# SAMV71_Xplained_Ultra_Connectors.net
KiCad netlist of a schematic drawn in Altium Designer
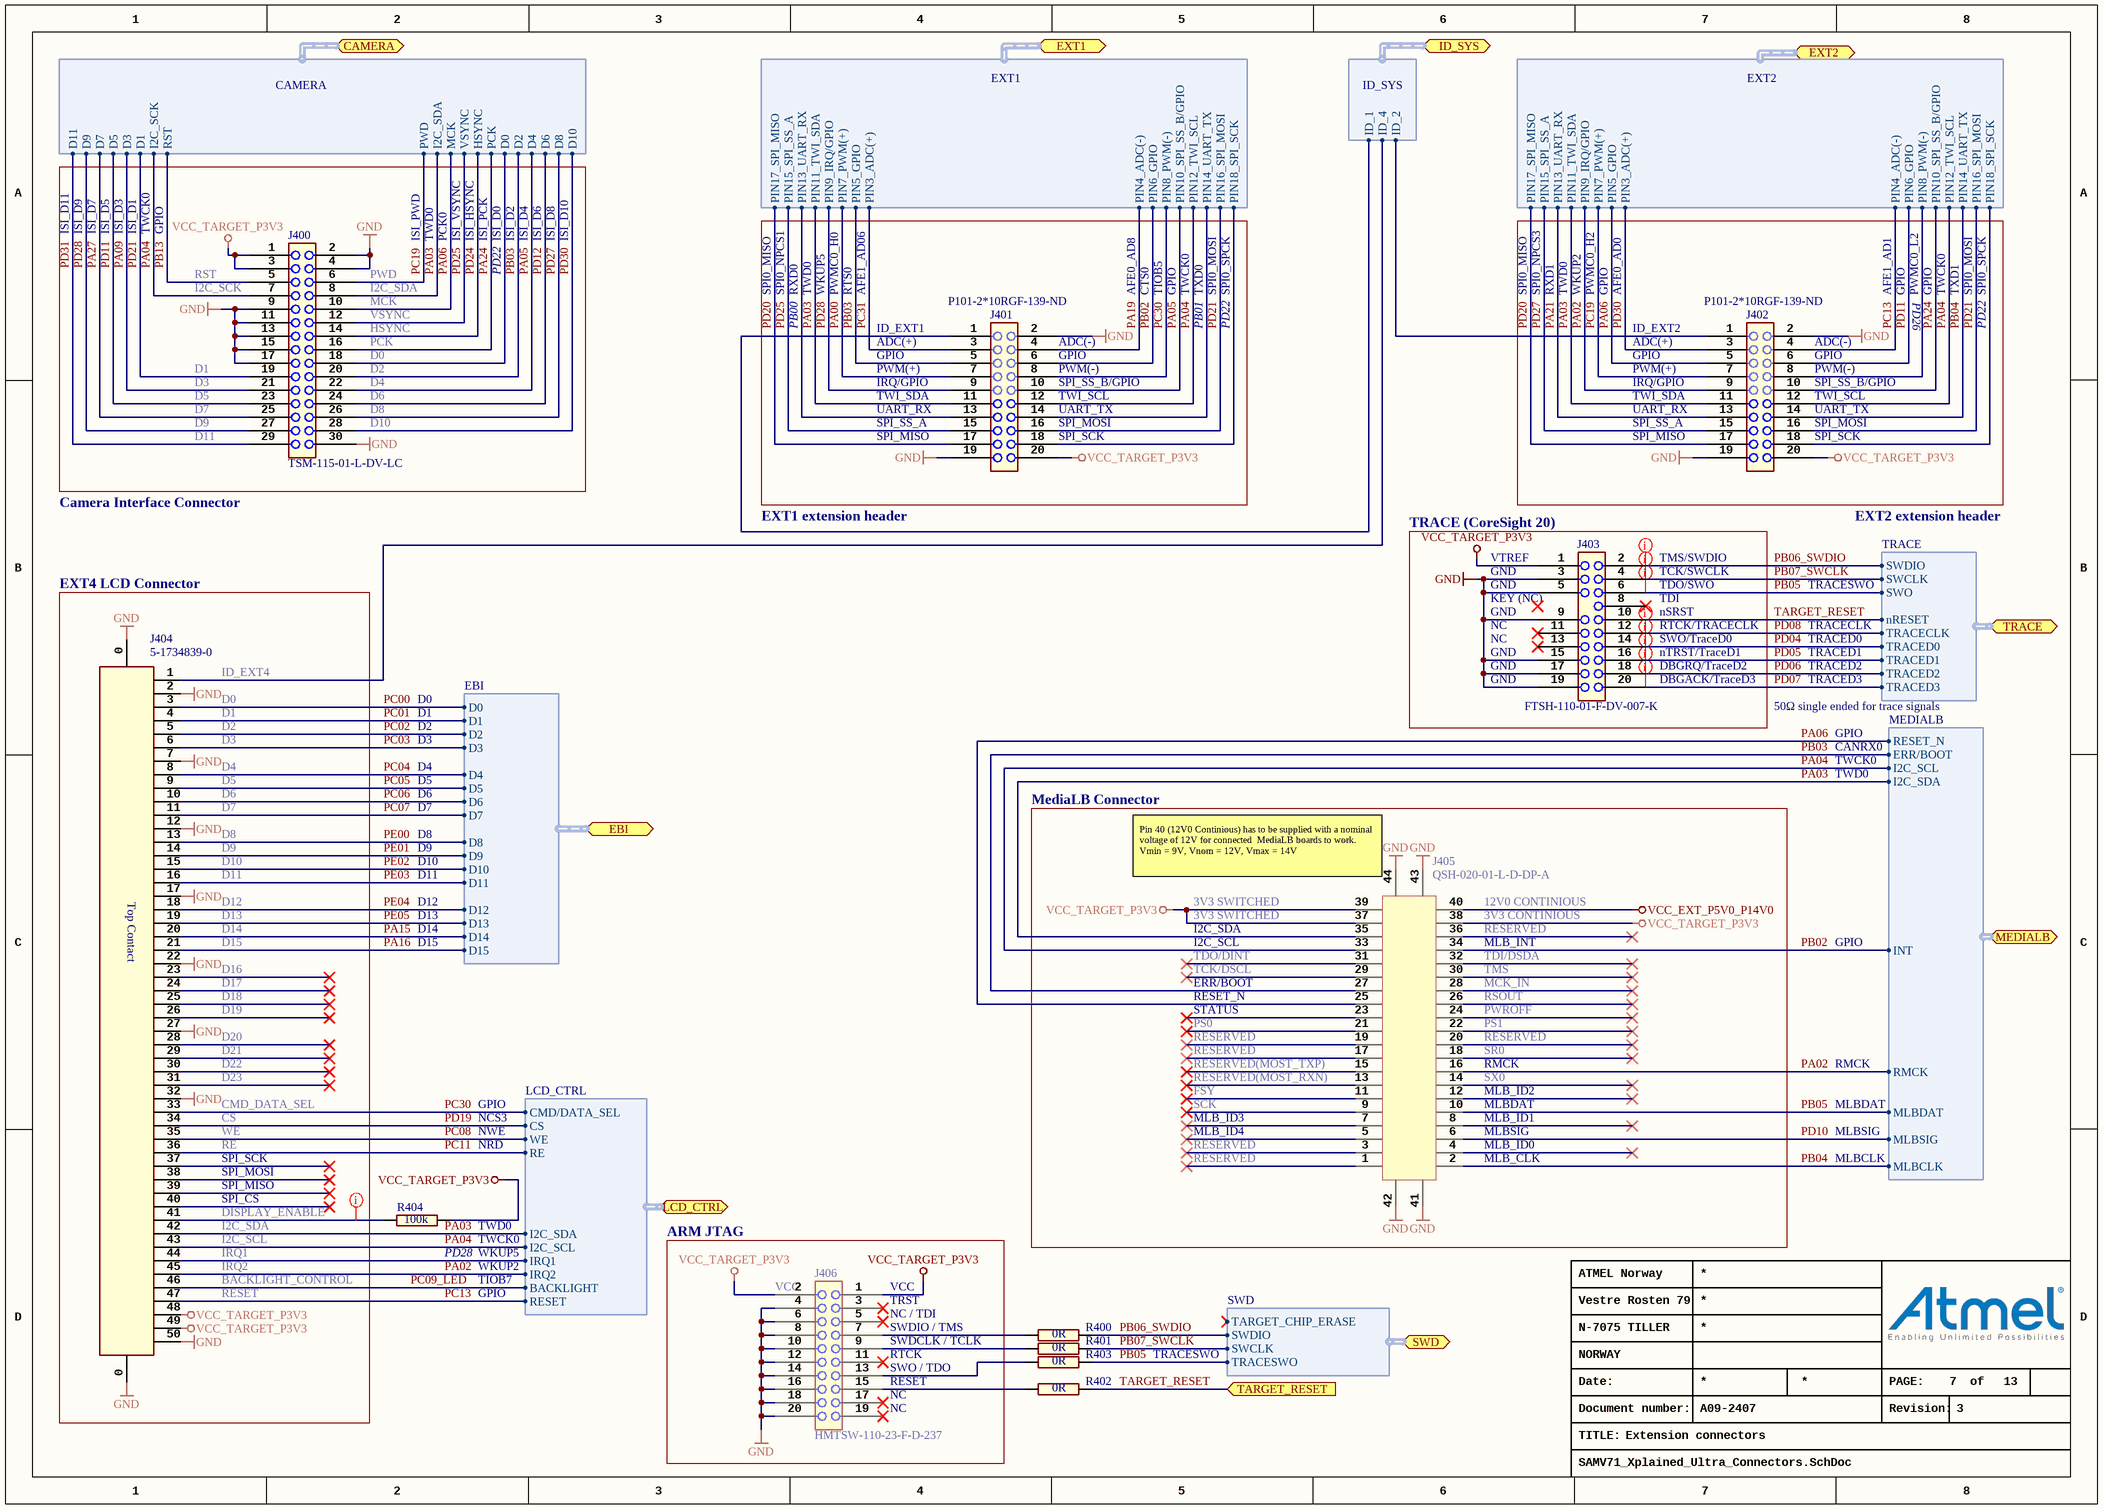
[diagram p0: SAMV71_Xplained_Ultra_Connectors.SchDoc]

(export (version "E")
  (design (tool "Eeschema 10.0.6"))
  (components
    (comp (ref "J400")
      (value "TSM-115-01-L-DV-LC")
      (footprint "AP8-00884")
      (description "Samtec TSM series, 2x15 pin header, straight, 2.54mm pitch SMD, locking leads.")
      (fields (field (name "MANUFACTURER") "SAMTEC"))
      (libsource (lib "AltiumDbLib") (part "HEADER 2x15"))
    )
    (comp (ref "J401")
      (value "P101-2*10RGF-139-ND")
      (footprint "AP8-00622")
      (description "Pin header, 2x10, Right Angle, 2.54mm, THM, Pin In Paste")
      (fields (field (name "MANUFACTURER") "Pro-data International Corp"))
      (libsource (lib "AltiumDbLib") (part "HEADER 2x10"))
    )
    (comp (ref "J402")
      (value "P101-2*10RGF-139-ND")
      (footprint "AP8-00622")
      (description "Pin header, 2x10, Right Angle, 2.54mm, THM, Pin In Paste")
      (fields (field (name "MANUFACTURER") "Pro-data International Corp"))
      (libsource (lib "AltiumDbLib") (part "HEADER 2x10"))
    )
    (comp (ref "J403")
      (value "FTSH-110-01-F-DV-007-K")
      (footprint "AP8-00910")
      (description "SAMTEC FTSH series 50-mil header, shrouded, pin 7 removed, SMD")
      (fields (field (name "MANUFACTURER") "SAMTEC"))
      (libsource (lib "AltiumDbLib") (part "FTSH-110-01-F-DV-007-K"))
    )
    (comp (ref "J404")
      (value "5-1734839-0")
      (footprint "AP8-00774")
      (description "50 pin FPC connector, e=0.5mm, single side contact (top).")
      (fields
        (field (name "MANUFACTURER") "TE Connectivity")
        (field (name "Comment") "Used for Xplained Pro MCU board on top layer.")
      )
      (libsource (lib "AltiumDbLib") (part "5-1734839-0"))
    )
    (comp (ref "J405")
      (value "QSH-020-01-L-D-DP-A")
      (footprint "AP8-00878")
      (description "SAMTEC 0.5mm, 20-pair, High-Speed Differential Pair Socket")
      (fields
        (field (name "MANUFACTURER") "SAMTEC")
        (field (name "Comment") "For SMSC MediaLB, \r\nMates with QTH-020-01-X-D-DP-XXX")
      )
      (libsource (lib "AltiumDbLib") (part "QSH-020-01-L-D-DP-A"))
    )
    (comp (ref "J406")
      (value "HMTSW-110-23-F-D-237")
      (footprint "AP8-00744")
      (description "2x10 pin header, 2.54mm pitch, Pin-in-Paste THM, 1mm hole")
      (fields (field (name "MANUFACTURER") "SAMTEC"))
      (libsource (lib "AltiumDbLib") (part "HEADER 2x10"))
    )
    (comp (ref "R400")
      (value "0R")
      (footprint "AP2-00000")
      (description "RES 0.0 OHM 1/16W 0402 SMD")
      (fields (field (name "TOLERANCE") "1 %") (field (name "MANUFACTURER") "(n/a)"))
      (libsource (lib "AltiumDbLib") (part "R2"))
    )
    (comp (ref "R401")
      (value "0R")
      (footprint "AP2-00000")
      (description "RES 0.0 OHM 1/16W 0402 SMD")
      (fields (field (name "TOLERANCE") "1 %") (field (name "MANUFACTURER") "(n/a)"))
      (libsource (lib "AltiumDbLib") (part "R2"))
    )
    (comp (ref "R402")
      (value "0R")
      (footprint "AP2-00000")
      (description "RES 0.0 OHM 1/16W 0402 SMD")
      (fields (field (name "TOLERANCE") "1 %") (field (name "MANUFACTURER") "(n/a)"))
      (libsource (lib "AltiumDbLib") (part "R2"))
    )
    (comp (ref "R403")
      (value "0R")
      (footprint "AP2-00000")
      (description "RES 0.0 OHM 1/16W 0402 SMD")
      (fields (field (name "TOLERANCE") "1 %") (field (name "MANUFACTURER") "(n/a)"))
      (libsource (lib "AltiumDbLib") (part "R2"))
    )
    (comp (ref "R404")
      (value "100k")
      (footprint "AP2-00011")
      (description "Thick film resistor, SMD 0402, 1/16W, 1%")
      (fields (field (name "TOLERANCE") "1 %"))
      (libsource (lib "") (part "R2_1"))
    )
  )
  (nets
    (net (code "10") (name "/ID_1") (class "Default")
      (node (ref "J401") (pin "1") (pinfunction "1_1") (pintype "passive"))
    )
    (net (code "11") (name "/ID_2") (class "Default")
      (node (ref "J402") (pin "1") (pinfunction "1_1") (pintype "passive"))
    )
    (net (code "12") (name "/ID_4") (class "Default")
      (node (ref "J404") (pin "1") (pinfunction "1_1") (pintype "passive"))
    )
    (net (code "13") (name "/IRQ1") (class "Default")
      (node (ref "J404") (pin "44") (pinfunction "44_44") (pintype "passive"))
    )
    (net (code "14") (name "/PA00") (class "Default")
      (node (ref "J401") (pin "7") (pinfunction "7_7") (pintype "passive"))
    )
    (net (code "15") (name "/PA02") (class "Default")
      (node (ref "J402") (pin "9") (pinfunction "9_9") (pintype "passive"))
      (node (ref "J404") (pin "45") (pinfunction "45_45") (pintype "passive"))
      (node (ref "J405") (pin "16") (pinfunction "16_16") (pintype "passive"))
    )
    (net (code "16") (name "/PA03") (class "Default")
      (node (ref "J400") (pin "8") (pinfunction "8_8") (pintype "passive"))
      (node (ref "J401") (pin "11") (pinfunction "11_11") (pintype "passive"))
      (node (ref "J402") (pin "11") (pinfunction "11_11") (pintype "passive"))
      (node (ref "J404") (pin "42") (pinfunction "42_42") (pintype "passive"))
      (node (ref "J405") (pin "35") (pinfunction "35_35") (pintype "passive"))
    )
    (net (code "17") (name "/PA04") (class "Default")
      (node (ref "J400") (pin "7") (pinfunction "7_7") (pintype "passive"))
      (node (ref "J401") (pin "12") (pinfunction "12_12") (pintype "passive"))
      (node (ref "J402") (pin "12") (pinfunction "12_12") (pintype "passive"))
      (node (ref "J404") (pin "43") (pinfunction "43_43") (pintype "passive"))
      (node (ref "J405") (pin "33") (pinfunction "33_33") (pintype "passive"))
    )
    (net (code "18") (name "/PA05") (class "Default")
      (node (ref "J400") (pin "22") (pinfunction "22_22") (pintype "passive"))
      (node (ref "J401") (pin "10") (pinfunction "10_10") (pintype "passive"))
    )
    (net (code "19") (name "/PA06") (class "Default")
      (node (ref "J400") (pin "10") (pinfunction "10_10") (pintype "passive"))
      (node (ref "J402") (pin "5") (pinfunction "5_5") (pintype "passive"))
      (node (ref "J405") (pin "25") (pinfunction "25_25") (pintype "passive"))
    )
    (net (code "20") (name "/PA09") (class "Default")
      (node (ref "J400") (pin "21") (pinfunction "21_21") (pintype "passive"))
    )
    (net (code "21") (name "/PA15") (class "Default")
      (node (ref "J404") (pin "20") (pinfunction "20_20") (pintype "passive"))
    )
    (net (code "22") (name "/PA16") (class "Default")
      (node (ref "J404") (pin "21") (pinfunction "21_21") (pintype "passive"))
    )
    (net (code "23") (name "/PA19") (class "Default")
      (node (ref "J401") (pin "4") (pinfunction "4_4") (pintype "passive"))
    )
    (net (code "24") (name "/PA21") (class "Default")
      (node (ref "J402") (pin "13") (pinfunction "13_13") (pintype "passive"))
    )
    (net (code "25") (name "/PA24") (class "Default")
      (node (ref "J400") (pin "16") (pinfunction "16_16") (pintype "passive"))
      (node (ref "J402") (pin "10") (pinfunction "10_10") (pintype "passive"))
    )
    (net (code "26") (name "/PA27") (class "Default")
      (node (ref "J400") (pin "25") (pinfunction "25_25") (pintype "passive"))
    )
    (net (code "27") (name "/PB02") (class "Default")
      (node (ref "J401") (pin "6") (pinfunction "6_6") (pintype "passive"))
      (node (ref "J405") (pin "34") (pinfunction "34_34") (pintype "passive"))
    )
    (net (code "28") (name "/PB03") (class "Default")
      (node (ref "J400") (pin "20") (pinfunction "20_20") (pintype "passive"))
      (node (ref "J401") (pin "5") (pinfunction "5_5") (pintype "passive"))
      (node (ref "J405") (pin "27") (pinfunction "27_27") (pintype "passive"))
    )
    (net (code "29") (name "/PB04") (class "Default")
      (node (ref "J402") (pin "14") (pinfunction "14_14") (pintype "passive"))
      (node (ref "J405") (pin "2") (pinfunction "2_2") (pintype "passive"))
    )
    (net (code "30") (name "/PB05") (class "Default")
      (node (ref "J403") (pin "6") (pinfunction "6_6") (pintype "passive"))
      (node (ref "J405") (pin "10") (pinfunction "10_10") (pintype "passive"))
      (node (ref "R403") (pin "2") (pinfunction "2_2") (pintype "passive"))
    )
    (net (code "31") (name "/PB06_SWDIO") (class "Default")
      (node (ref "J403") (pin "2") (pinfunction "2_2") (pintype "passive"))
      (node (ref "R400") (pin "2") (pinfunction "2_2") (pintype "passive"))
    )
    (net (code "32") (name "/PB07_SWCLK") (class "Default")
      (node (ref "J403") (pin "4") (pinfunction "4_4") (pintype "passive"))
      (node (ref "R401") (pin "2") (pinfunction "2_2") (pintype "passive"))
    )
    (net (code "33") (name "/PB13") (class "Default")
      (node (ref "J400") (pin "5") (pinfunction "5_5") (pintype "passive"))
    )
    (net (code "34") (name "/PC00") (class "Default")
      (node (ref "J404") (pin "3") (pinfunction "3_3") (pintype "passive"))
    )
    (net (code "35") (name "/PC01") (class "Default")
      (node (ref "J404") (pin "4") (pinfunction "4_4") (pintype "passive"))
    )
    (net (code "36") (name "/PC02") (class "Default")
      (node (ref "J404") (pin "5") (pinfunction "5_5") (pintype "passive"))
    )
    (net (code "37") (name "/PC03") (class "Default")
      (node (ref "J404") (pin "6") (pinfunction "6_6") (pintype "passive"))
    )
    (net (code "38") (name "/PC04") (class "Default")
      (node (ref "J404") (pin "8") (pinfunction "8_8") (pintype "passive"))
    )
    (net (code "39") (name "/PC05") (class "Default")
      (node (ref "J404") (pin "9") (pinfunction "9_9") (pintype "passive"))
    )
    (net (code "40") (name "/PC06") (class "Default")
      (node (ref "J404") (pin "10") (pinfunction "10_10") (pintype "passive"))
    )
    (net (code "41") (name "/PC07") (class "Default")
      (node (ref "J404") (pin "11") (pinfunction "11_11") (pintype "passive"))
    )
    (net (code "42") (name "/PC08") (class "Default")
      (node (ref "J404") (pin "35") (pinfunction "35_35") (pintype "passive"))
    )
    (net (code "43") (name "/PC09_LED") (class "Default")
      (node (ref "J404") (pin "46") (pinfunction "46_46") (pintype "passive"))
    )
    (net (code "44") (name "/PC11") (class "Default")
      (node (ref "J404") (pin "36") (pinfunction "36_36") (pintype "passive"))
    )
    (net (code "45") (name "/PC13") (class "Default")
      (node (ref "J402") (pin "4") (pinfunction "4_4") (pintype "passive"))
      (node (ref "J404") (pin "47") (pinfunction "47_47") (pintype "passive"))
    )
    (net (code "46") (name "/PC19") (class "Default")
      (node (ref "J400") (pin "6") (pinfunction "6_6") (pintype "passive"))
      (node (ref "J402") (pin "7") (pinfunction "7_7") (pintype "passive"))
    )
    (net (code "47") (name "/PC30") (class "Default")
      (node (ref "J401") (pin "8") (pinfunction "8_8") (pintype "passive"))
      (node (ref "J404") (pin "33") (pinfunction "33_33") (pintype "passive"))
    )
    (net (code "48") (name "/PC31") (class "Default")
      (node (ref "J401") (pin "3") (pinfunction "3_3") (pintype "passive"))
    )
    (net (code "49") (name "/PD04") (class "Default")
      (node (ref "J403") (pin "14") (pinfunction "14_14") (pintype "passive"))
    )
    (net (code "50") (name "/PD05") (class "Default")
      (node (ref "J403") (pin "16") (pinfunction "16_16") (pintype "passive"))
    )
    (net (code "51") (name "/PD06") (class "Default")
      (node (ref "J403") (pin "18") (pinfunction "18_18") (pintype "passive"))
    )
    (net (code "52") (name "/PD07") (class "Default")
      (node (ref "J403") (pin "20") (pinfunction "20_20") (pintype "passive"))
    )
    (net (code "53") (name "/PD08") (class "Default")
      (node (ref "J403") (pin "12") (pinfunction "12_12") (pintype "passive"))
    )
    (net (code "54") (name "/PD10") (class "Default")
      (node (ref "J405") (pin "6") (pinfunction "6_6") (pintype "passive"))
    )
    (net (code "55") (name "/PD11") (class "Default")
      (node (ref "J400") (pin "23") (pinfunction "23_23") (pintype "passive"))
      (node (ref "J402") (pin "6") (pinfunction "6_6") (pintype "passive"))
    )
    (net (code "56") (name "/PD12") (class "Default")
      (node (ref "J400") (pin "24") (pinfunction "24_24") (pintype "passive"))
    )
    (net (code "57") (name "/PD19") (class "Default")
      (node (ref "J404") (pin "34") (pinfunction "34_34") (pintype "passive"))
    )
    (net (code "58") (name "/PD20") (class "Default")
      (node (ref "J401") (pin "17") (pinfunction "17_17") (pintype "passive"))
      (node (ref "J402") (pin "17") (pinfunction "17_17") (pintype "passive"))
    )
    (net (code "59") (name "/PD21") (class "Default")
      (node (ref "J400") (pin "19") (pinfunction "19_19") (pintype "passive"))
      (node (ref "J401") (pin "16") (pinfunction "16_16") (pintype "passive"))
      (node (ref "J402") (pin "16") (pinfunction "16_16") (pintype "passive"))
    )
    (net (code "60") (name "/PD24") (class "Default")
      (node (ref "J400") (pin "14") (pinfunction "14_14") (pintype "passive"))
    )
    (net (code "61") (name "/PD25") (class "Default")
      (node (ref "J400") (pin "12") (pinfunction "12_12") (pintype "passive"))
      (node (ref "J401") (pin "15") (pinfunction "15_15") (pintype "passive"))
    )
    (net (code "62") (name "/PD27") (class "Default")
      (node (ref "J400") (pin "26") (pinfunction "26_26") (pintype "passive"))
      (node (ref "J402") (pin "15") (pinfunction "15_15") (pintype "passive"))
    )
    (net (code "63") (name "/PD28") (class "Default")
      (node (ref "J400") (pin "27") (pinfunction "27_27") (pintype "passive"))
      (node (ref "J401") (pin "9") (pinfunction "9_9") (pintype "passive"))
    )
    (net (code "64") (name "/PD30") (class "Default")
      (node (ref "J400") (pin "28") (pinfunction "28_28") (pintype "passive"))
      (node (ref "J402") (pin "3") (pinfunction "3_3") (pintype "passive"))
    )
    (net (code "65") (name "/PD31") (class "Default")
      (node (ref "J400") (pin "29") (pinfunction "29_29") (pintype "passive"))
    )
    (net (code "66") (name "/PE00") (class "Default")
      (node (ref "J404") (pin "13") (pinfunction "13_13") (pintype "passive"))
    )
    (net (code "67") (name "/PE01") (class "Default")
      (node (ref "J404") (pin "14") (pinfunction "14_14") (pintype "passive"))
    )
    (net (code "68") (name "/PE02") (class "Default")
      (node (ref "J404") (pin "15") (pinfunction "15_15") (pintype "passive"))
    )
    (net (code "69") (name "/PE03") (class "Default")
      (node (ref "J404") (pin "16") (pinfunction "16_16") (pintype "passive"))
    )
    (net (code "70") (name "/PE04") (class "Default")
      (node (ref "J404") (pin "18") (pinfunction "18_18") (pintype "passive"))
    )
    (net (code "71") (name "/PE05") (class "Default")
      (node (ref "J404") (pin "19") (pinfunction "19_19") (pintype "passive"))
    )
    (net (code "72") (name "/TARGET_RESET") (class "Default")
      (node (ref "J403") (pin "10") (pinfunction "10_10") (pintype "passive"))
      (node (ref "R402") (pin "2") (pinfunction "2_2") (pintype "passive"))
    )
    (net (code "82") (name "GND") (class "Default")
      (node (ref "J400") (pin "11") (pinfunction "11_11") (pintype "passive"))
      (node (ref "J400") (pin "13") (pinfunction "13_13") (pintype "passive"))
      (node (ref "J400") (pin "15") (pinfunction "15_15") (pintype "passive"))
      (node (ref "J400") (pin "17") (pinfunction "17_17") (pintype "passive"))
      (node (ref "J400") (pin "2") (pinfunction "2_2") (pintype "passive"))
      (node (ref "J400") (pin "30") (pinfunction "30_30") (pintype "passive"))
      (node (ref "J400") (pin "4") (pinfunction "4_4") (pintype "passive"))
      (node (ref "J400") (pin "9") (pinfunction "9_9") (pintype "passive"))
      (node (ref "J401") (pin "19") (pinfunction "19_19") (pintype "passive"))
      (node (ref "J401") (pin "2") (pinfunction "2_2") (pintype "passive"))
      (node (ref "J402") (pin "19") (pinfunction "19_19") (pintype "passive"))
      (node (ref "J402") (pin "2") (pinfunction "2_2") (pintype "passive"))
      (node (ref "J403") (pin "15") (pinfunction "15_15") (pintype "passive"))
      (node (ref "J403") (pin "17") (pinfunction "17_17") (pintype "passive"))
      (node (ref "J403") (pin "19") (pinfunction "19_19") (pintype "passive"))
      (node (ref "J403") (pin "3") (pinfunction "3_3") (pintype "passive"))
      (node (ref "J403") (pin "5") (pinfunction "5_5") (pintype "passive"))
      (node (ref "J403") (pin "9") (pinfunction "9_9") (pintype "passive"))
      (node (ref "J404") (pin "0") (pinfunction "1_0") (pintype "passive"))
      (node (ref "J404") (pin "12") (pinfunction "12_12") (pintype "passive"))
      (node (ref "J404") (pin "17") (pinfunction "17_17") (pintype "passive"))
      (node (ref "J404") (pin "2") (pinfunction "2_2") (pintype "passive"))
      (node (ref "J404") (pin "22") (pinfunction "22_22") (pintype "passive"))
      (node (ref "J404") (pin "27") (pinfunction "27_27") (pintype "passive"))
      (node (ref "J404") (pin "32") (pinfunction "32_32") (pintype "passive"))
      (node (ref "J404") (pin "50") (pinfunction "50_50") (pintype "passive"))
      (node (ref "J404") (pin "7") (pinfunction "7_7") (pintype "passive"))
      (node (ref "J405") (pin "41") (pinfunction "41_41") (pintype "passive"))
      (node (ref "J405") (pin "42") (pinfunction "42_42") (pintype "passive"))
      (node (ref "J405") (pin "43") (pinfunction "43_43") (pintype "passive"))
      (node (ref "J405") (pin "44") (pinfunction "44_44") (pintype "passive"))
      (node (ref "J406") (pin "10") (pinfunction "10_10") (pintype "passive"))
      (node (ref "J406") (pin "12") (pinfunction "12_12") (pintype "passive"))
      (node (ref "J406") (pin "14") (pinfunction "14_14") (pintype "passive"))
      (node (ref "J406") (pin "16") (pinfunction "16_16") (pintype "passive"))
      (node (ref "J406") (pin "18") (pinfunction "18_18") (pintype "passive"))
      (node (ref "J406") (pin "20") (pinfunction "20_20") (pintype "passive"))
      (node (ref "J406") (pin "4") (pinfunction "4_4") (pintype "passive"))
      (node (ref "J406") (pin "6") (pinfunction "6_6") (pintype "passive"))
      (node (ref "J406") (pin "8") (pinfunction "8_8") (pintype "passive"))
    )
    (net (code "83") (name "Net-(J404-Pad41)") (class "Default")
      (node (ref "J404") (pin "41") (pinfunction "41_41") (pintype "passive"))
      (node (ref "R404") (pin "2") (pinfunction "2_2") (pintype "passive"))
    )
    (net (code "84") (name "Net-(J406-Pad7)") (class "Default")
      (node (ref "J406") (pin "7") (pinfunction "7_7") (pintype "passive"))
      (node (ref "R400") (pin "1") (pinfunction "1_1") (pintype "passive"))
    )
    (net (code "85") (name "Net-(J406-Pad9)") (class "Default")
      (node (ref "J406") (pin "9") (pinfunction "9_9") (pintype "passive"))
      (node (ref "R401") (pin "1") (pinfunction "1_1") (pintype "passive"))
    )
    (net (code "86") (name "Net-(J406-Pad13)") (class "Default")
      (node (ref "J406") (pin "13") (pinfunction "13_13") (pintype "passive"))
      (node (ref "R403") (pin "1") (pinfunction "1_1") (pintype "passive"))
    )
    (net (code "87") (name "Net-(J406-Pad15)") (class "Default")
      (node (ref "J406") (pin "15") (pinfunction "15_15") (pintype "passive"))
      (node (ref "R402") (pin "1") (pinfunction "1_1") (pintype "passive"))
    )
    (net (code "88") (name "VCC_EXT_P5V0_P14V0") (class "Default")
      (node (ref "J405") (pin "40") (pinfunction "40_40") (pintype "passive"))
    )
    (net (code "89") (name "VCC_TARGET_P3V3") (class "Default")
      (node (ref "J400") (pin "1") (pinfunction "1_1") (pintype "passive"))
      (node (ref "J400") (pin "3") (pinfunction "3_3") (pintype "passive"))
      (node (ref "J401") (pin "20") (pinfunction "20_20") (pintype "passive"))
      (node (ref "J402") (pin "20") (pinfunction "20_20") (pintype "passive"))
      (node (ref "J403") (pin "1") (pinfunction "1_1") (pintype "passive"))
      (node (ref "J404") (pin "48") (pinfunction "48_48") (pintype "passive"))
      (node (ref "J404") (pin "49") (pinfunction "49_49") (pintype "passive"))
      (node (ref "J405") (pin "37") (pinfunction "37_37") (pintype "passive"))
      (node (ref "J405") (pin "38") (pinfunction "38_38") (pintype "passive"))
      (node (ref "J405") (pin "39") (pinfunction "39_39") (pintype "passive"))
      (node (ref "J406") (pin "1") (pinfunction "1_1") (pintype "passive"))
      (node (ref "J406") (pin "2") (pinfunction "2_2") (pintype "passive"))
      (node (ref "R404") (pin "1") (pinfunction "1_1") (pintype "passive"))
    )
    (net (code "90") (name "unconnected-(J400-Pad18)") (class "Default")
      (node (ref "J400") (pin "18") (pinfunction "18_18") (pintype "passive"))
    )
    (net (code "91") (name "unconnected-(J401-Pad13)") (class "Default")
      (node (ref "J401") (pin "13") (pinfunction "13_13") (pintype "passive"))
    )
    (net (code "92") (name "unconnected-(J401-Pad14)") (class "Default")
      (node (ref "J401") (pin "14") (pinfunction "14_14") (pintype "passive"))
    )
    (net (code "93") (name "unconnected-(J401-Pad18)") (class "Default")
      (node (ref "J401") (pin "18") (pinfunction "18_18") (pintype "passive"))
    )
    (net (code "94") (name "unconnected-(J402-Pad8)") (class "Default")
      (node (ref "J402") (pin "8") (pinfunction "8_8") (pintype "passive"))
    )
    (net (code "95") (name "unconnected-(J402-Pad18)") (class "Default")
      (node (ref "J402") (pin "18") (pinfunction "18_18") (pintype "passive"))
    )
    (net (code "96") (name "unconnected-(J403-Pad8)") (class "Default")
      (node (ref "J403") (pin "8") (pinfunction "8_8") (pintype "passive+no_connect"))
    )
    (net (code "97") (name "unconnected-(J403-Pad11)") (class "Default")
      (node (ref "J403") (pin "11") (pinfunction "11_11") (pintype "passive+no_connect"))
    )
    (net (code "98") (name "unconnected-(J403-Pad13)") (class "Default")
      (node (ref "J403") (pin "13") (pinfunction "13_13") (pintype "passive+no_connect"))
    )
    (net (code "99") (name "unconnected-(J404-Pad23)") (class "Default")
      (node (ref "J404") (pin "23") (pinfunction "23_23") (pintype "passive+no_connect"))
    )
    (net (code "100") (name "unconnected-(J404-Pad24)") (class "Default")
      (node (ref "J404") (pin "24") (pinfunction "24_24") (pintype "passive+no_connect"))
    )
    (net (code "101") (name "unconnected-(J404-Pad25)") (class "Default")
      (node (ref "J404") (pin "25") (pinfunction "25_25") (pintype "passive+no_connect"))
    )
    (net (code "102") (name "unconnected-(J404-Pad26)") (class "Default")
      (node (ref "J404") (pin "26") (pinfunction "26_26") (pintype "passive+no_connect"))
    )
    (net (code "103") (name "unconnected-(J404-Pad28)") (class "Default")
      (node (ref "J404") (pin "28") (pinfunction "28_28") (pintype "passive+no_connect"))
    )
    (net (code "104") (name "unconnected-(J404-Pad29)") (class "Default")
      (node (ref "J404") (pin "29") (pinfunction "29_29") (pintype "passive+no_connect"))
    )
    (net (code "105") (name "unconnected-(J404-Pad30)") (class "Default")
      (node (ref "J404") (pin "30") (pinfunction "30_30") (pintype "passive+no_connect"))
    )
    (net (code "106") (name "unconnected-(J404-Pad31)") (class "Default")
      (node (ref "J404") (pin "31") (pinfunction "31_31") (pintype "passive+no_connect"))
    )
    (net (code "107") (name "unconnected-(J404-Pad37)") (class "Default")
      (node (ref "J404") (pin "37") (pinfunction "37_37") (pintype "passive+no_connect"))
    )
    (net (code "108") (name "unconnected-(J404-Pad38)") (class "Default")
      (node (ref "J404") (pin "38") (pinfunction "38_38") (pintype "passive+no_connect"))
    )
    (net (code "109") (name "unconnected-(J404-Pad39)") (class "Default")
      (node (ref "J404") (pin "39") (pinfunction "39_39") (pintype "passive+no_connect"))
    )
    (net (code "110") (name "unconnected-(J404-Pad40)") (class "Default")
      (node (ref "J404") (pin "40") (pinfunction "40_40") (pintype "passive+no_connect"))
    )
    (net (code "111") (name "unconnected-(J405-Pad1)") (class "Default")
      (node (ref "J405") (pin "1") (pinfunction "1_1") (pintype "passive+no_connect"))
    )
    (net (code "112") (name "unconnected-(J405-Pad3)") (class "Default")
      (node (ref "J405") (pin "3") (pinfunction "3_3") (pintype "passive+no_connect"))
    )
    (net (code "113") (name "unconnected-(J405-Pad4)") (class "Default")
      (node (ref "J405") (pin "4") (pinfunction "4_4") (pintype "passive+no_connect"))
    )
    (net (code "114") (name "unconnected-(J405-Pad5)") (class "Default")
      (node (ref "J405") (pin "5") (pinfunction "5_5") (pintype "passive+no_connect"))
    )
    (net (code "115") (name "unconnected-(J405-Pad7)") (class "Default")
      (node (ref "J405") (pin "7") (pinfunction "7_7") (pintype "passive+no_connect"))
    )
    (net (code "116") (name "unconnected-(J405-Pad8)") (class "Default")
      (node (ref "J405") (pin "8") (pinfunction "8_8") (pintype "passive+no_connect"))
    )
    (net (code "117") (name "unconnected-(J405-Pad9)") (class "Default")
      (node (ref "J405") (pin "9") (pinfunction "9_9") (pintype "passive+no_connect"))
    )
    (net (code "118") (name "unconnected-(J405-Pad11)") (class "Default")
      (node (ref "J405") (pin "11") (pinfunction "11_11") (pintype "passive+no_connect"))
    )
    (net (code "119") (name "unconnected-(J405-Pad12)") (class "Default")
      (node (ref "J405") (pin "12") (pinfunction "12_12") (pintype "passive+no_connect"))
    )
    (net (code "120") (name "unconnected-(J405-Pad13)") (class "Default")
      (node (ref "J405") (pin "13") (pinfunction "13_13") (pintype "passive+no_connect"))
    )
    (net (code "121") (name "unconnected-(J405-Pad14)") (class "Default")
      (node (ref "J405") (pin "14") (pinfunction "14_14") (pintype "passive+no_connect"))
    )
    (net (code "122") (name "unconnected-(J405-Pad15)") (class "Default")
      (node (ref "J405") (pin "15") (pinfunction "15_15") (pintype "passive+no_connect"))
    )
    (net (code "123") (name "unconnected-(J405-Pad17)") (class "Default")
      (node (ref "J405") (pin "17") (pinfunction "17_17") (pintype "passive+no_connect"))
    )
    (net (code "124") (name "unconnected-(J405-Pad18)") (class "Default")
      (node (ref "J405") (pin "18") (pinfunction "18_18") (pintype "passive+no_connect"))
    )
    (net (code "125") (name "unconnected-(J405-Pad19)") (class "Default")
      (node (ref "J405") (pin "19") (pinfunction "19_19") (pintype "passive+no_connect"))
    )
    (net (code "126") (name "unconnected-(J405-Pad20)") (class "Default")
      (node (ref "J405") (pin "20") (pinfunction "20_20") (pintype "passive+no_connect"))
    )
    (net (code "127") (name "unconnected-(J405-Pad21)") (class "Default")
      (node (ref "J405") (pin "21") (pinfunction "21_21") (pintype "passive+no_connect"))
    )
    (net (code "128") (name "unconnected-(J405-Pad22)") (class "Default")
      (node (ref "J405") (pin "22") (pinfunction "22_22") (pintype "passive+no_connect"))
    )
    (net (code "129") (name "unconnected-(J405-Pad23)") (class "Default")
      (node (ref "J405") (pin "23") (pinfunction "23_23") (pintype "passive+no_connect"))
    )
    (net (code "130") (name "unconnected-(J405-Pad24)") (class "Default")
      (node (ref "J405") (pin "24") (pinfunction "24_24") (pintype "passive+no_connect"))
    )
    (net (code "131") (name "unconnected-(J405-Pad26)") (class "Default")
      (node (ref "J405") (pin "26") (pinfunction "26_26") (pintype "passive+no_connect"))
    )
    (net (code "132") (name "unconnected-(J405-Pad28)") (class "Default")
      (node (ref "J405") (pin "28") (pinfunction "28_28") (pintype "passive+no_connect"))
    )
    (net (code "133") (name "unconnected-(J405-Pad29)") (class "Default")
      (node (ref "J405") (pin "29") (pinfunction "29_29") (pintype "passive+no_connect"))
    )
    (net (code "134") (name "unconnected-(J405-Pad30)") (class "Default")
      (node (ref "J405") (pin "30") (pinfunction "30_30") (pintype "passive+no_connect"))
    )
    (net (code "135") (name "unconnected-(J405-Pad31)") (class "Default")
      (node (ref "J405") (pin "31") (pinfunction "31_31") (pintype "passive+no_connect"))
    )
    (net (code "136") (name "unconnected-(J405-Pad32)") (class "Default")
      (node (ref "J405") (pin "32") (pinfunction "32_32") (pintype "passive+no_connect"))
    )
    (net (code "137") (name "unconnected-(J405-Pad36)") (class "Default")
      (node (ref "J405") (pin "36") (pinfunction "36_36") (pintype "passive+no_connect"))
    )
    (net (code "138") (name "unconnected-(J406-Pad3)") (class "Default")
      (node (ref "J406") (pin "3") (pinfunction "3_3") (pintype "passive+no_connect"))
    )
    (net (code "139") (name "unconnected-(J406-Pad5)") (class "Default")
      (node (ref "J406") (pin "5") (pinfunction "5_5") (pintype "passive+no_connect"))
    )
    (net (code "140") (name "unconnected-(J406-Pad11)") (class "Default")
      (node (ref "J406") (pin "11") (pinfunction "11_11") (pintype "passive+no_connect"))
    )
    (net (code "141") (name "unconnected-(J406-Pad17)") (class "Default")
      (node (ref "J406") (pin "17") (pinfunction "17_17") (pintype "passive+no_connect"))
    )
    (net (code "142") (name "unconnected-(J406-Pad19)") (class "Default")
      (node (ref "J406") (pin "19") (pinfunction "19_19") (pintype "passive+no_connect"))
    )
  )
)
